# CAN-BT.net
KiCad netlist of a schematic drawn in EAGLE
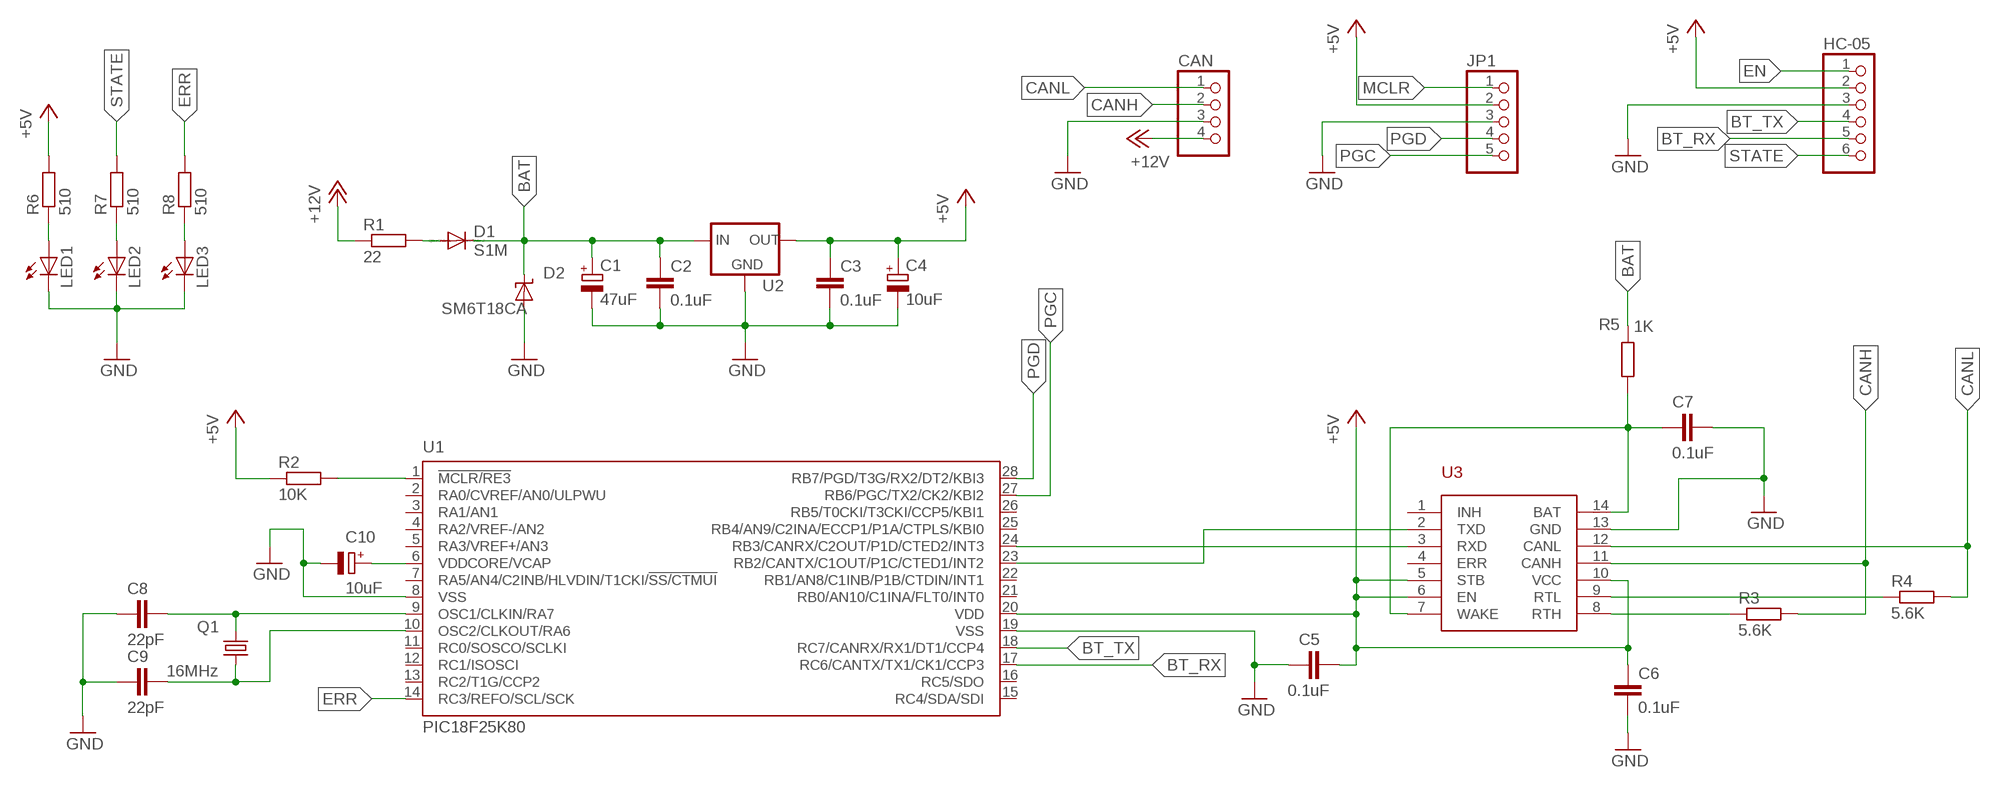
[diagram p0: schematic, sheet 1]

(export (version "E")
  (design (tool "Eeschema 10.0.6"))
  (components
    (comp (ref "C1")
      (value "47uF")
      (footprint "eagle-import:153CLV-0807")
      (libsource (lib "eagle-import") (part "CPOL-EU153CLV-0807"))
    )
    (comp (ref "C2")
      (value "0.1uF")
      (footprint "eagle-import:C0805")
      (libsource (lib "eagle-import") (part "C-EUC0805"))
    )
    (comp (ref "C3")
      (value "0.1uF")
      (footprint "eagle-import:C0805")
      (libsource (lib "eagle-import") (part "C-EUC0805"))
    )
    (comp (ref "C4")
      (value "10uF")
      (footprint "eagle-import:153CLV-0605")
      (libsource (lib "eagle-import") (part "CPOL-EU153CLV-0605"))
    )
    (comp (ref "C5")
      (value "0.1uF")
      (footprint "eagle-import:C0805")
      (libsource (lib "eagle-import") (part "C-EUC0805"))
    )
    (comp (ref "C6")
      (value "0.1uF")
      (footprint "eagle-import:C0805")
      (libsource (lib "eagle-import") (part "C-EUC0805"))
    )
    (comp (ref "C7")
      (value "0.1uF")
      (footprint "eagle-import:C0805")
      (libsource (lib "eagle-import") (part "C-EUC0805"))
    )
    (comp (ref "C8")
      (value "22pF")
      (footprint "eagle-import:C0805")
      (libsource (lib "eagle-import") (part "C-EUC0805"))
    )
    (comp (ref "C9")
      (value "22pF")
      (footprint "eagle-import:C0805")
      (libsource (lib "eagle-import") (part "C-EUC0805"))
    )
    (comp (ref "C10")
      (value "10uF")
      (footprint "eagle-import:SMC_A")
      (libsource (lib "eagle-import") (part "CPOL-EUSMCA"))
    )
    (comp (ref "CAN")
      (value "PINHD-1X4")
      (footprint "eagle-import:1X04")
      (libsource (lib "eagle-import") (part "PINHD-1X4"))
    )
    (comp (ref "D1")
      (value "S1M")
      (footprint "eagle-import:SMA")
      (libsource (lib "eagle-import") (part "S1M"))
    )
    (comp (ref "D2")
      (value "SM6T18CA")
      (footprint "eagle-import:SMBJ")
      (libsource (lib "eagle-import") (part "SUPPRESSOR-SMBJ"))
    )
    (comp (ref "HC-05")
      (value "PINHD-1X6")
      (footprint "eagle-import:1X06")
      (libsource (lib "eagle-import") (part "PINHD-1X6"))
    )
    (comp (ref "JP1")
      (value "PINHD-1X5")
      (footprint "eagle-import:1X05")
      (libsource (lib "eagle-import") (part "PINHD-1X5"))
    )
    (comp (ref "LED1")
      (value "LEDSQR2X5")
      (footprint "eagle-import:LED2X5")
      (libsource (lib "eagle-import") (part "LEDSQR2X5"))
    )
    (comp (ref "LED2")
      (value "LEDSQR2X5")
      (footprint "eagle-import:LED2X5")
      (libsource (lib "eagle-import") (part "LEDSQR2X5"))
    )
    (comp (ref "LED3")
      (value "LEDSQR2X5")
      (footprint "eagle-import:LED2X5")
      (libsource (lib "eagle-import") (part "LEDSQR2X5"))
    )
    (comp (ref "Q1")
      (value "16MHz")
      (footprint "eagle-import:HC49_S")
      (libsource (lib "eagle-import") (part "CRYSTALHC49S"))
    )
    (comp (ref "R1")
      (value "22")
      (footprint "eagle-import:M1206")
      (libsource (lib "eagle-import") (part "R-EU_M1206"))
    )
    (comp (ref "R2")
      (value "10K")
      (footprint "eagle-import:R0805")
      (libsource (lib "eagle-import") (part "R-EU_R0805"))
    )
    (comp (ref "R3")
      (value "5.6K")
      (footprint "eagle-import:R0805")
      (libsource (lib "eagle-import") (part "R-EU_R0805"))
    )
    (comp (ref "R4")
      (value "5.6K")
      (footprint "eagle-import:R0805")
      (libsource (lib "eagle-import") (part "R-EU_R0805"))
    )
    (comp (ref "R5")
      (value "1K")
      (footprint "eagle-import:R0805")
      (libsource (lib "eagle-import") (part "R-EU_R0805"))
    )
    (comp (ref "R6")
      (value "510")
      (footprint "eagle-import:R0805")
      (libsource (lib "eagle-import") (part "R-EU_R0805"))
    )
    (comp (ref "R7")
      (value "510")
      (footprint "eagle-import:R0805")
      (libsource (lib "eagle-import") (part "R-EU_R0805"))
    )
    (comp (ref "R8")
      (value "510")
      (footprint "eagle-import:R0805")
      (libsource (lib "eagle-import") (part "R-EU_R0805"))
    )
    (comp (ref "U1")
      (value "PIC18F25K80")
      (footprint "eagle-import:SO28W")
      (libsource (lib "eagle-import") (part "PIC18F25K80"))
    )
    (comp (ref "U2")
      (value "78M05")
      (footprint "eagle-import:DPACK")
      (libsource (lib "eagle-import") (part "78M05"))
    )
    (comp (ref "U3")
      (value "TJA1055T")
      (footprint "eagle-import:SO-14W")
      (libsource (lib "eagle-import") (part "TJA1055T"))
    )
  )
  (nets
    (net (code "1") (name "+5V") (class "Default")
      (node (ref "C3") (pin "1") (pinfunction "1_1") (pintype "passive"))
      (node (ref "C4") (pin "+") (pinfunction "+_+") (pintype "passive"))
      (node (ref "C5") (pin "1") (pinfunction "1_1") (pintype "passive"))
      (node (ref "C6") (pin "1") (pinfunction "1_1") (pintype "passive"))
      (node (ref "HC-05") (pin "2") (pinfunction "2_2") (pintype "passive"))
      (node (ref "JP1") (pin "2") (pinfunction "2_2") (pintype "passive"))
      (node (ref "R2") (pin "1") (pinfunction "1_1") (pintype "passive"))
      (node (ref "R6") (pin "2") (pinfunction "2_2") (pintype "passive"))
      (node (ref "U1") (pin "20") (pinfunction "VDD_20") (pintype "power_in"))
      (node (ref "U2") (pin "3") (pinfunction "OUT_3") (pintype "passive"))
      (node (ref "U3") (pin "10") (pinfunction "VCC_10") (pintype "power_in"))
      (node (ref "U3") (pin "5") (pinfunction "STB_5") (pintype "input"))
      (node (ref "U3") (pin "6") (pinfunction "EN_6") (pintype "input"))
    )
    (net (code "2") (name "+12V") (class "Default")
      (node (ref "CAN") (pin "4") (pinfunction "4_4") (pintype "passive"))
      (node (ref "R1") (pin "1") (pinfunction "1_1") (pintype "passive"))
    )
    (net (code "3") (name "BAT") (class "Default")
      (node (ref "C1") (pin "+") (pinfunction "+_+") (pintype "passive"))
      (node (ref "C2") (pin "1") (pinfunction "1_1") (pintype "passive"))
      (node (ref "D1") (pin "C") (pinfunction "C_C") (pintype "passive"))
      (node (ref "D2") (pin "C") (pinfunction "C_C") (pintype "passive"))
      (node (ref "R5") (pin "2") (pinfunction "2_2") (pintype "passive"))
      (node (ref "U2") (pin "1") (pinfunction "IN_1") (pintype "input"))
    )
    (net (code "4") (name "BT_RX") (class "Default")
      (node (ref "HC-05") (pin "5") (pinfunction "5_5") (pintype "passive"))
      (node (ref "U1") (pin "17") (pinfunction "RC6/CANTX/TX1/CK1/CCP3_17") (pintype "bidirectional"))
    )
    (net (code "5") (name "BT_TX") (class "Default")
      (node (ref "HC-05") (pin "4") (pinfunction "4_4") (pintype "passive"))
      (node (ref "U1") (pin "18") (pinfunction "RC7/CANRX/RX1/DT1/CCP4_18") (pintype "bidirectional"))
    )
    (net (code "6") (name "CANH") (class "Default")
      (node (ref "CAN") (pin "2") (pinfunction "2_2") (pintype "passive"))
      (node (ref "R3") (pin "2") (pinfunction "2_2") (pintype "passive"))
      (node (ref "U3") (pin "11") (pinfunction "CANH_11") (pintype "bidirectional"))
    )
    (net (code "7") (name "CANL") (class "Default")
      (node (ref "CAN") (pin "1") (pinfunction "1_1") (pintype "passive"))
      (node (ref "R4") (pin "2") (pinfunction "2_2") (pintype "passive"))
      (node (ref "U3") (pin "12") (pinfunction "CANL_12") (pintype "bidirectional"))
    )
    (net (code "8") (name "EN") (class "Default")
      (node (ref "HC-05") (pin "1") (pinfunction "1_1") (pintype "passive"))
    )
    (net (code "9") (name "ERR") (class "Default")
      (node (ref "R8") (pin "2") (pinfunction "2_2") (pintype "passive"))
      (node (ref "U1") (pin "14") (pinfunction "RC3/REFO/SCL/SCK_14") (pintype "bidirectional"))
    )
    (net (code "10") (name "GND") (class "Default")
      (node (ref "C1") (pin "-") (pinfunction "-_-") (pintype "passive"))
      (node (ref "C10") (pin "-") (pinfunction "-_-") (pintype "passive"))
      (node (ref "C2") (pin "2") (pinfunction "2_2") (pintype "passive"))
      (node (ref "C3") (pin "2") (pinfunction "2_2") (pintype "passive"))
      (node (ref "C4") (pin "-") (pinfunction "-_-") (pintype "passive"))
      (node (ref "C5") (pin "2") (pinfunction "2_2") (pintype "passive"))
      (node (ref "C6") (pin "2") (pinfunction "2_2") (pintype "passive"))
      (node (ref "C7") (pin "2") (pinfunction "2_2") (pintype "passive"))
      (node (ref "C8") (pin "1") (pinfunction "1_1") (pintype "passive"))
      (node (ref "C9") (pin "1") (pinfunction "1_1") (pintype "passive"))
      (node (ref "CAN") (pin "3") (pinfunction "3_3") (pintype "passive"))
      (node (ref "D2") (pin "A") (pinfunction "A_A") (pintype "passive"))
      (node (ref "HC-05") (pin "3") (pinfunction "3_3") (pintype "passive"))
      (node (ref "JP1") (pin "3") (pinfunction "3_3") (pintype "passive"))
      (node (ref "LED1") (pin "K") (pinfunction "C_K") (pintype "passive"))
      (node (ref "LED2") (pin "K") (pinfunction "C_K") (pintype "passive"))
      (node (ref "LED3") (pin "K") (pinfunction "C_K") (pintype "passive"))
      (node (ref "U1") (pin "19") (pinfunction "VSS_19") (pintype "power_in"))
      (node (ref "U1") (pin "8") (pinfunction "VSS_8") (pintype "power_in"))
      (node (ref "U2") (pin "4") (pinfunction "GND_4") (pintype "input"))
      (node (ref "U3") (pin "13") (pinfunction "GND_13") (pintype "power_in"))
    )
    (net (code "11") (name "MCLR") (class "Default")
      (node (ref "JP1") (pin "1") (pinfunction "1_1") (pintype "passive"))
    )
    (net (code "12") (name "Net-(D1-PadA)") (class "Default")
      (node (ref "D1") (pin "A") (pinfunction "A_A") (pintype "passive"))
      (node (ref "R1") (pin "2") (pinfunction "2_2") (pintype "passive"))
    )
    (net (code "13") (name "Net-(LED1-PadA)") (class "Default")
      (node (ref "LED1") (pin "A") (pinfunction "A_A") (pintype "passive"))
      (node (ref "R6") (pin "1") (pinfunction "1_1") (pintype "passive"))
    )
    (net (code "14") (name "Net-(LED2-PadA)") (class "Default")
      (node (ref "LED2") (pin "A") (pinfunction "A_A") (pintype "passive"))
      (node (ref "R7") (pin "1") (pinfunction "1_1") (pintype "passive"))
    )
    (net (code "15") (name "Net-(LED3-PadA)") (class "Default")
      (node (ref "LED3") (pin "A") (pinfunction "A_A") (pintype "passive"))
      (node (ref "R8") (pin "1") (pinfunction "1_1") (pintype "passive"))
    )
    (net (code "16") (name "Net-(U1-OSC1{slash}CLKIN{slash}RA7)") (class "Default")
      (node (ref "C8") (pin "2") (pinfunction "2_2") (pintype "passive"))
      (node (ref "Q1") (pin "1") (pinfunction "1_1") (pintype "passive"))
      (node (ref "U1") (pin "9") (pinfunction "OSC1/CLKIN/RA7_9") (pintype "input"))
    )
    (net (code "17") (name "Net-(U1-OSC2{slash}CLKOUT{slash}RA6)") (class "Default")
      (node (ref "C9") (pin "2") (pinfunction "2_2") (pintype "passive"))
      (node (ref "Q1") (pin "2") (pinfunction "2_2") (pintype "passive"))
      (node (ref "U1") (pin "10") (pinfunction "OSC2/CLKOUT/RA6_10") (pintype "output"))
    )
    (net (code "18") (name "Net-(U1-RB2{slash}CANTX{slash}C1OUT{slash}P1C{slash}CTED1{slash}INT2)") (class "Default")
      (node (ref "U1") (pin "23") (pinfunction "RB2/CANTX/C1OUT/P1C/CTED1/INT2_23") (pintype "bidirectional"))
      (node (ref "U3") (pin "2") (pinfunction "TXD_2") (pintype "bidirectional"))
    )
    (net (code "19") (name "Net-(U1-RB3{slash}CANRX{slash}C2OUT{slash}P1D{slash}CTED2{slash}INT3)") (class "Default")
      (node (ref "U1") (pin "24") (pinfunction "RB3/CANRX/C2OUT/P1D/CTED2/INT3_24") (pintype "bidirectional"))
      (node (ref "U3") (pin "3") (pinfunction "RXD_3") (pintype "bidirectional"))
    )
    (net (code "20") (name "Net-(U1-VDDCORE{slash}VCAP)") (class "Default")
      (node (ref "C10") (pin "+") (pinfunction "+_+") (pintype "passive"))
      (node (ref "U1") (pin "6") (pinfunction "VDDCORE/VCAP_6") (pintype "bidirectional"))
    )
    (net (code "21") (name "Net-(U1-~{MCLR{slash}RE3})") (class "Default")
      (node (ref "R2") (pin "2") (pinfunction "2_2") (pintype "passive"))
      (node (ref "U1") (pin "1") (pinfunction "~{MCLR/RE3}_1") (pintype "input"))
    )
    (net (code "22") (name "Net-(U3-BAT)") (class "Default")
      (node (ref "C7") (pin "1") (pinfunction "1_1") (pintype "passive"))
      (node (ref "R5") (pin "1") (pinfunction "1_1") (pintype "passive"))
      (node (ref "U3") (pin "14") (pinfunction "BAT_14") (pintype "input"))
      (node (ref "U3") (pin "7") (pinfunction "WAKE_7") (pintype "input"))
    )
    (net (code "23") (name "Net-(U3-RTH)") (class "Default")
      (node (ref "R3") (pin "1") (pinfunction "1_1") (pintype "passive"))
      (node (ref "U3") (pin "8") (pinfunction "RTH_8") (pintype "bidirectional"))
    )
    (net (code "24") (name "Net-(U3-RTL)") (class "Default")
      (node (ref "R4") (pin "1") (pinfunction "1_1") (pintype "passive"))
      (node (ref "U3") (pin "9") (pinfunction "RTL_9") (pintype "bidirectional"))
    )
    (net (code "25") (name "PGC") (class "Default")
      (node (ref "JP1") (pin "5") (pinfunction "5_5") (pintype "passive"))
      (node (ref "U1") (pin "27") (pinfunction "RB6/PGC/TX2/CK2/KBI2_27") (pintype "bidirectional"))
    )
    (net (code "26") (name "PGD") (class "Default")
      (node (ref "JP1") (pin "4") (pinfunction "4_4") (pintype "passive"))
      (node (ref "U1") (pin "28") (pinfunction "RB7/PGD/T3G/RX2/DT2/KBI3_28") (pintype "bidirectional"))
    )
    (net (code "27") (name "STATE") (class "Default")
      (node (ref "HC-05") (pin "6") (pinfunction "6_6") (pintype "passive"))
      (node (ref "R7") (pin "2") (pinfunction "2_2") (pintype "passive"))
    )
    (net (code "28") (name "unconnected-(U1-RA0{slash}CVREF{slash}AN0{slash}ULPWU-Pad2)") (class "Default")
      (node (ref "U1") (pin "2") (pinfunction "RA0/CVREF/AN0/ULPWU_2") (pintype "bidirectional"))
    )
    (net (code "29") (name "unconnected-(U1-RA1{slash}AN1-Pad3)") (class "Default")
      (node (ref "U1") (pin "3") (pinfunction "RA1/AN1_3") (pintype "bidirectional"))
    )
    (net (code "30") (name "unconnected-(U1-RA2{slash}VREF-{slash}AN2-Pad4)") (class "Default")
      (node (ref "U1") (pin "4") (pinfunction "RA2/VREF-/AN2_4") (pintype "bidirectional"))
    )
    (net (code "31") (name "unconnected-(U1-RA3{slash}VREF+{slash}AN3-Pad5)") (class "Default")
      (node (ref "U1") (pin "5") (pinfunction "RA3/VREF+/AN3_5") (pintype "bidirectional"))
    )
    (net (code "32") (name "unconnected-(U1-RA5{slash}AN4{slash}C2INB{slash}HLVDIN{slash}T1CKI{slash}~{SS{slash}CTMUI}-Pad7)") (class "Default")
      (node (ref "U1") (pin "7") (pinfunction "RA5/AN4/C2INB/HLVDIN/T1CKI/~{SS/CTMUI}_7") (pintype "bidirectional"))
    )
    (net (code "33") (name "unconnected-(U1-RB0{slash}AN10{slash}C1INA{slash}FLT0{slash}INT0-Pad21)") (class "Default")
      (node (ref "U1") (pin "21") (pinfunction "RB0/AN10/C1INA/FLT0/INT0_21") (pintype "bidirectional"))
    )
    (net (code "34") (name "unconnected-(U1-RB1{slash}AN8{slash}C1INB{slash}P1B{slash}CTDIN{slash}INT1-Pad22)") (class "Default")
      (node (ref "U1") (pin "22") (pinfunction "RB1/AN8/C1INB/P1B/CTDIN/INT1_22") (pintype "bidirectional"))
    )
    (net (code "35") (name "unconnected-(U1-RB4{slash}AN9{slash}C2INA{slash}ECCP1{slash}P1A{slash}CTPLS{slash}KBI0-Pad25)") (class "Default")
      (node (ref "U1") (pin "25") (pinfunction "RB4/AN9/C2INA/ECCP1/P1A/CTPLS/KBI0_25") (pintype "bidirectional"))
    )
    (net (code "36") (name "unconnected-(U1-RB5{slash}T0CKI{slash}T3CKI{slash}CCP5{slash}KBI1-Pad26)") (class "Default")
      (node (ref "U1") (pin "26") (pinfunction "RB5/T0CKI/T3CKI/CCP5/KBI1_26") (pintype "bidirectional"))
    )
    (net (code "37") (name "unconnected-(U1-RC0{slash}SOSCO{slash}SCLKI-Pad11)") (class "Default")
      (node (ref "U1") (pin "11") (pinfunction "RC0/SOSCO/SCLKI_11") (pintype "bidirectional"))
    )
    (net (code "38") (name "unconnected-(U1-RC1{slash}ISOSCI-Pad12)") (class "Default")
      (node (ref "U1") (pin "12") (pinfunction "RC1/ISOSCI_12") (pintype "bidirectional"))
    )
    (net (code "39") (name "unconnected-(U1-RC2{slash}T1G{slash}CCP2-Pad13)") (class "Default")
      (node (ref "U1") (pin "13") (pinfunction "RC2/T1G/CCP2_13") (pintype "bidirectional"))
    )
    (net (code "40") (name "unconnected-(U1-RC4{slash}SDA{slash}SDI-Pad15)") (class "Default")
      (node (ref "U1") (pin "15") (pinfunction "RC4/SDA/SDI_15") (pintype "bidirectional"))
    )
    (net (code "41") (name "unconnected-(U1-RC5{slash}SDO-Pad16)") (class "Default")
      (node (ref "U1") (pin "16") (pinfunction "RC5/SDO_16") (pintype "bidirectional"))
    )
    (net (code "42") (name "unconnected-(U3-ERR-Pad4)") (class "Default")
      (node (ref "U3") (pin "4") (pinfunction "ERR_4") (pintype "output"))
    )
    (net (code "43") (name "unconnected-(U3-INH-Pad1)") (class "Default")
      (node (ref "U3") (pin "1") (pinfunction "INH_1") (pintype "output"))
    )
  )
)
